# FPGAPower_Misc.net
KiCad netlist of a schematic drawn in Altium Designer
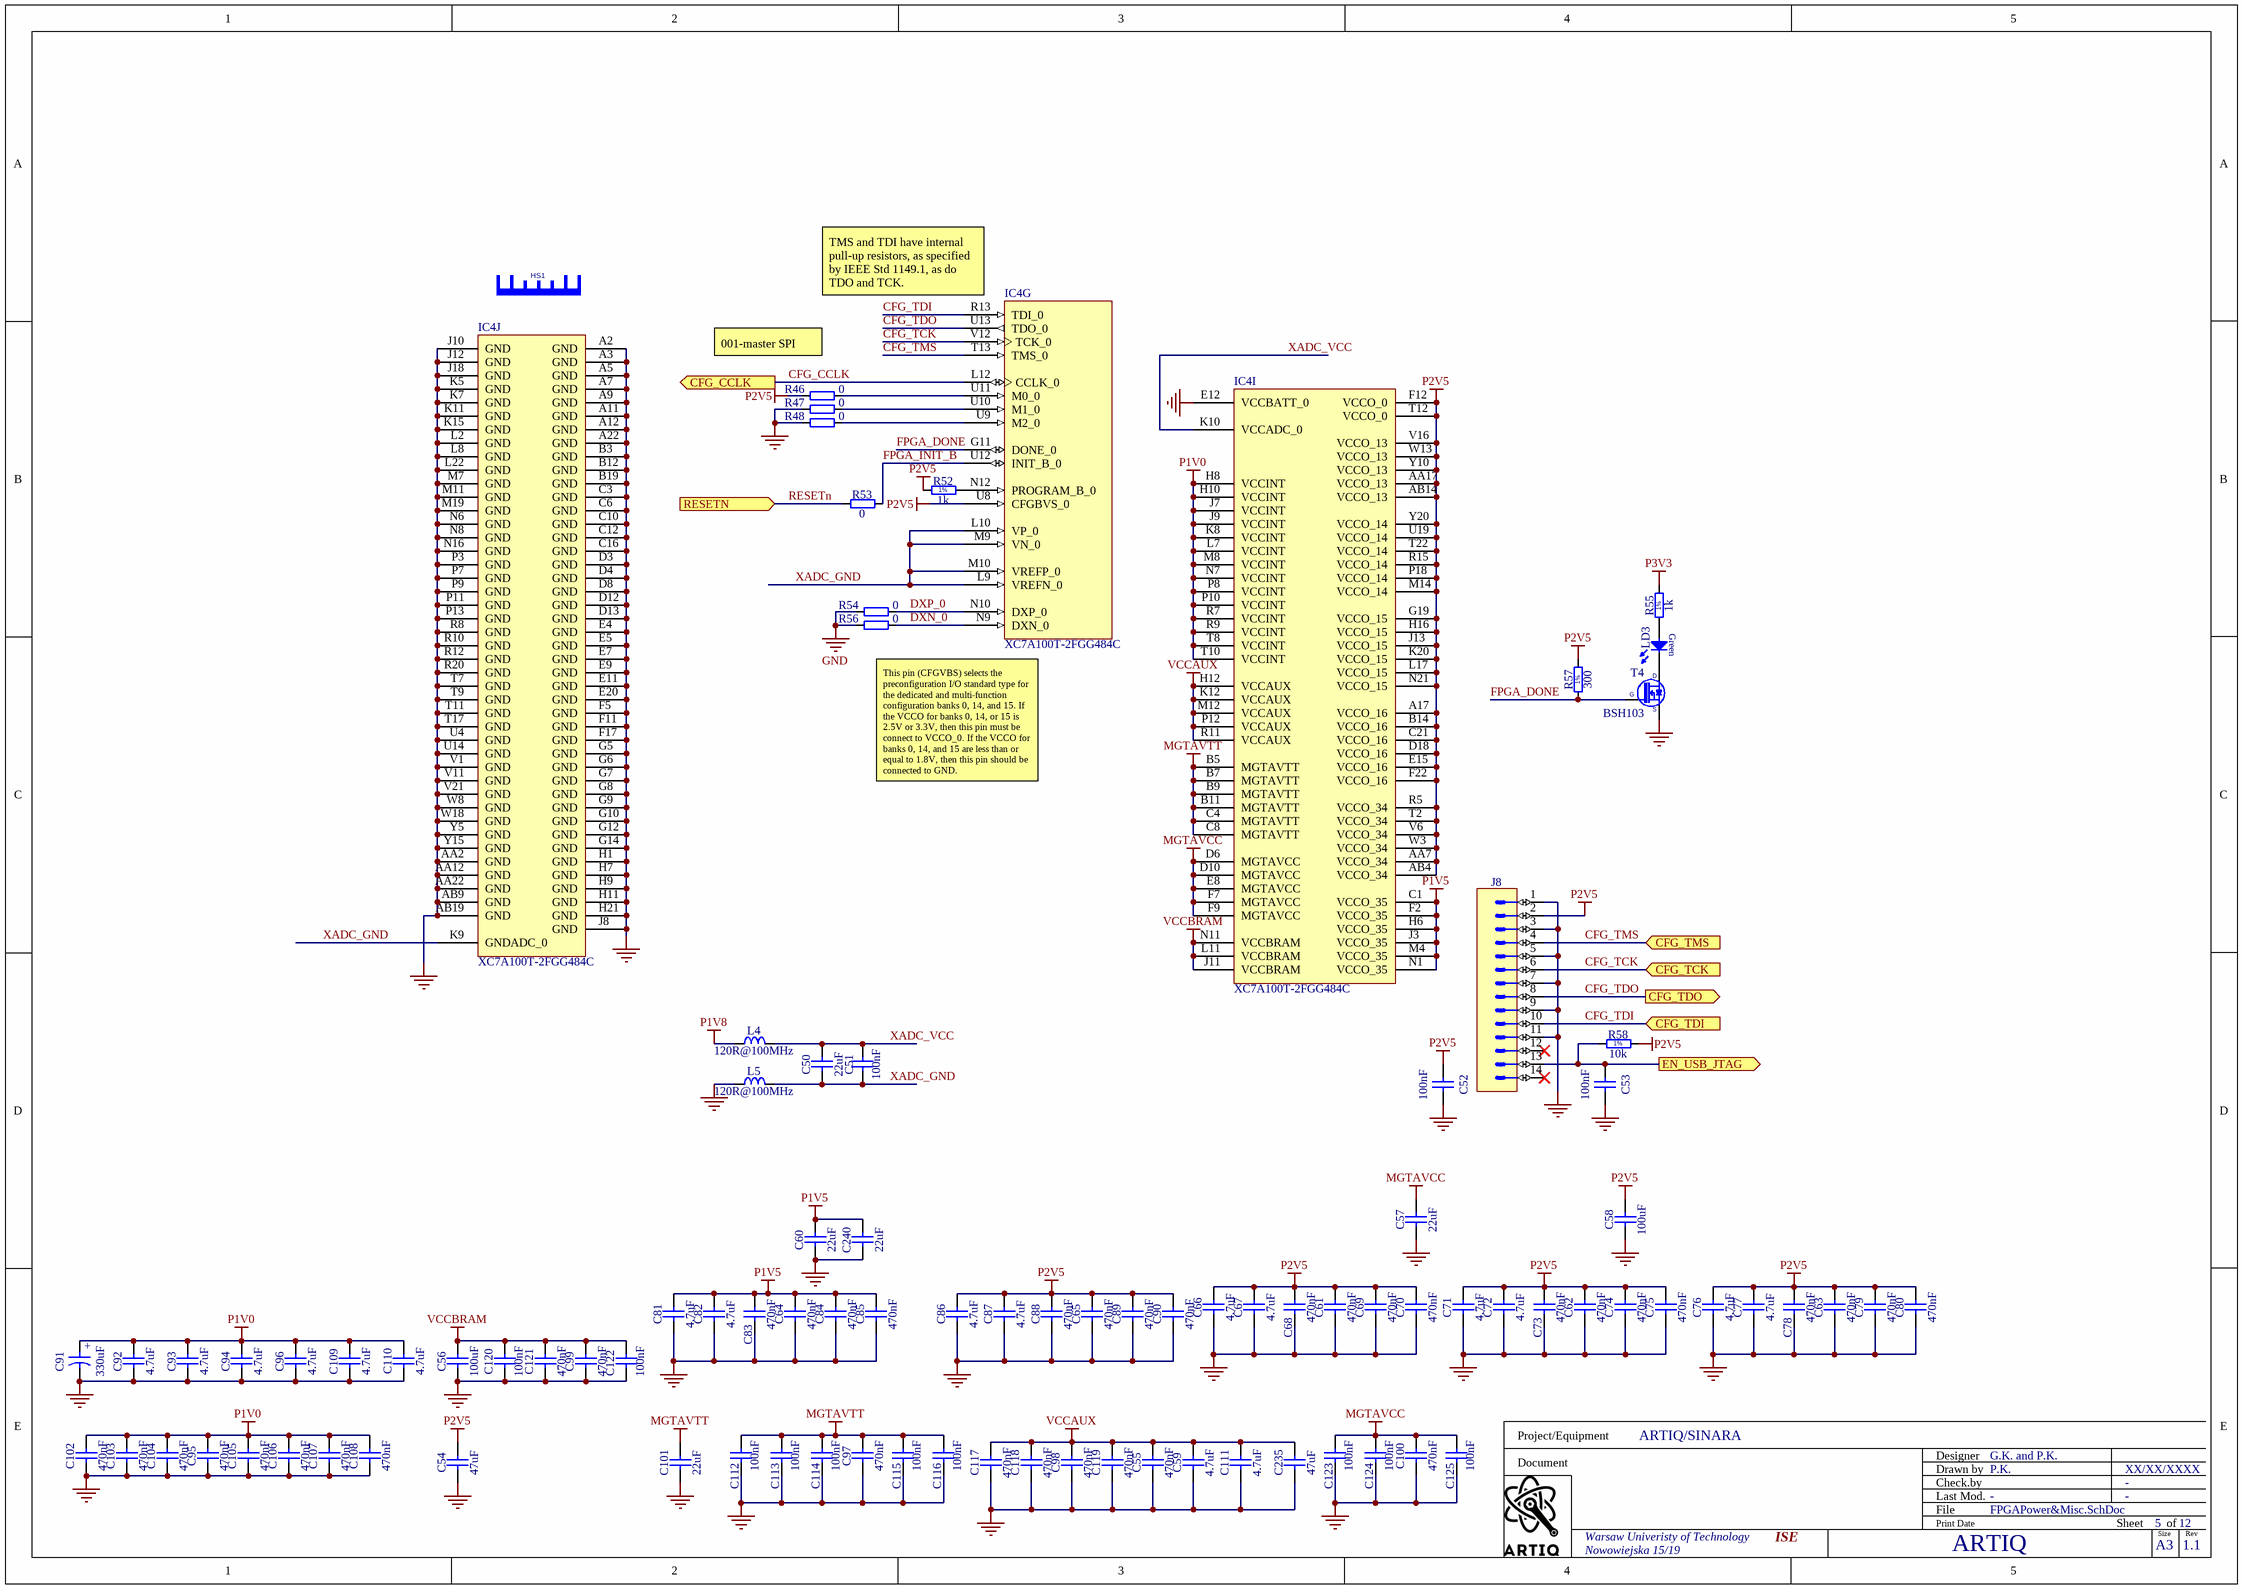
[diagram p0: FPGAPower&Misc.SchDoc]

(export (version "E")
  (design (tool "Eeschema 10.0.6"))
  (components
    (comp (ref "C50")
      (value "22uF")
      (footprint "CAPC1709X100N")
      (description "Non-polarised capacitor")
      (fields
        (field (name "PART NUMBER") "CC0603_22UF_6.3V_20%_X5R")
        (field (name "VOLTAGE") "6.3V")
        (field (name "AUTHOR") "CERN DEM JLC")
      )
      (libsource (lib "Capacitors") (part "Capacitor - non polarized"))
    )
    (comp (ref "C51")
      (value "100nF")
      (footprint "CAPC0603X33N")
      (description "Non-polarised capacitor")
      (fields
        (field (name "PART NUMBER") "CC0201_100NF_6.3V_10%_X5R")
        (field (name "VOLTAGE") "6.3V")
        (field (name "AUTHOR") "CERN DEM JLC")
      )
      (libsource (lib "Capacitors") (part "Capacitor - non polarized"))
    )
    (comp (ref "C52")
      (value "100nF")
      (footprint "CAPC0603X33N")
      (description "Non-polarised capacitor")
      (fields
        (field (name "PART NUMBER") "CC0201_100NF_6.3V_10%_X5R")
        (field (name "VOLTAGE") "6.3V")
        (field (name "AUTHOR") "CERN DEM JLC")
      )
      (libsource (lib "Capacitors") (part "Capacitor - non polarized"))
    )
    (comp (ref "C53")
      (value "100nF")
      (footprint "CAPC0603X33N")
      (description "Non-polarised capacitor")
      (fields
        (field (name "PART NUMBER") "CC0201_100NF_6.3V_10%_X5R")
        (field (name "VOLTAGE") "6.3V")
        (field (name "AUTHOR") "CERN DEM JLC")
      )
      (libsource (lib "Capacitors") (part "Capacitor - non polarized"))
    )
    (comp (ref "C54")
      (value "47uF")
      (footprint "CAPC3225X270N")
      (description "Non-polarised capacitor")
      (fields
        (field (name "PART NUMBER") "CC1210_47UF_10V_10%_X7R")
        (field (name "VOLTAGE") "10V")
        (field (name "AUTHOR") "CERN DEM BC")
      )
      (libsource (lib "Capacitors") (part "Capacitor - non polarized"))
    )
    (comp (ref "C55")
      (value "470nF")
      (footprint "CAPC0603X33N")
      (description "Non-polarised capacitor")
      (fields
        (field (name "PART NUMBER") "CC0201_470NF_4V_20%_X5R")
        (field (name "VOLTAGE") "4V")
        (field (name "AUTHOR") "CERN DEM JLC")
      )
      (libsource (lib "Capacitors") (part "Capacitor - non polarized"))
    )
    (comp (ref "C56")
      (value "100uF")
      (footprint "CAPC3225X270N")
      (description "Non-polarised capacitor")
      (fields
        (field (name "PART NUMBER") "CC1210_100UF_6.3V_20%_X5R")
        (field (name "VOLTAGE") "6.3V")
        (field (name "AUTHOR") "CERN DEM JLC")
      )
      (libsource (lib "Capacitors") (part "Capacitor - non polarized"))
    )
    (comp (ref "C57")
      (value "22uF")
      (footprint "CAPC1709X100N")
      (description "Non-polarised capacitor")
      (fields
        (field (name "PART NUMBER") "CC0603_22UF_6.3V_20%_X5R")
        (field (name "VOLTAGE") "6.3V")
        (field (name "AUTHOR") "CERN DEM JLC")
      )
      (libsource (lib "Capacitors") (part "Capacitor - non polarized"))
    )
    (comp (ref "C58")
      (value "100uF")
      (footprint "CAPC3225X270N")
      (description "Non-polarised capacitor")
      (fields
        (field (name "PART NUMBER") "CC1210_100UF_6.3V_20%_X5R")
        (field (name "VOLTAGE") "6.3V")
        (field (name "AUTHOR") "CERN DEM JLC")
      )
      (libsource (lib "Capacitors") (part "Capacitor - non polarized"))
    )
    (comp (ref "C59")
      (value "4.7uF")
      (footprint "CAPC2012X135N")
      (description "Non-polarised capacitor")
      (fields
        (field (name "MANUFACTURER") "GENERIC")
        (field (name "PART NUMBER") "CC0805_4.7UF_10V_10%_X5R")
        (field (name "AUTHOR") "CERN DEM JLC")
      )
      (libsource (lib "Capacitors") (part "Capacitor - non polarized"))
    )
    (comp (ref "C60")
      (value "22uF")
      (footprint "CAPC1709X100N")
      (description "Non-polarised capacitor")
      (fields
        (field (name "PART NUMBER") "CC0603_22UF_6.3V_20%_X5R")
        (field (name "VOLTAGE") "6.3V")
        (field (name "AUTHOR") "CERN DEM JLC")
      )
      (libsource (lib "Capacitors") (part "Capacitor - non polarized"))
    )
    (comp (ref "C61")
      (value "470nF")
      (footprint "CAPC0603X33N")
      (description "Non-polarised capacitor")
      (fields
        (field (name "PART NUMBER") "CC0201_470NF_4V_20%_X5R")
        (field (name "VOLTAGE") "4V")
        (field (name "AUTHOR") "CERN DEM JLC")
      )
      (libsource (lib "Capacitors") (part "Capacitor - non polarized"))
    )
    (comp (ref "C62")
      (value "470nF")
      (footprint "CAPC0603X33N")
      (description "Non-polarised capacitor")
      (fields
        (field (name "PART NUMBER") "CC0201_470NF_4V_20%_X5R")
        (field (name "VOLTAGE") "4V")
        (field (name "AUTHOR") "CERN DEM JLC")
      )
      (libsource (lib "Capacitors") (part "Capacitor - non polarized"))
    )
    (comp (ref "C63")
      (value "470nF")
      (footprint "CAPC0603X33N")
      (description "Non-polarised capacitor")
      (fields
        (field (name "PART NUMBER") "CC0201_470NF_4V_20%_X5R")
        (field (name "VOLTAGE") "4V")
        (field (name "AUTHOR") "CERN DEM JLC")
      )
      (libsource (lib "Capacitors") (part "Capacitor - non polarized"))
    )
    (comp (ref "C64")
      (value "470nF")
      (footprint "CAPC0603X33N")
      (description "Non-polarised capacitor")
      (fields
        (field (name "PART NUMBER") "CC0201_470NF_4V_20%_X5R")
        (field (name "VOLTAGE") "4V")
        (field (name "AUTHOR") "CERN DEM JLC")
      )
      (libsource (lib "Capacitors") (part "Capacitor - non polarized"))
    )
    (comp (ref "C65")
      (value "470nF")
      (footprint "CAPC0603X33N")
      (description "Non-polarised capacitor")
      (fields
        (field (name "PART NUMBER") "CC0201_470NF_4V_20%_X5R")
        (field (name "VOLTAGE") "4V")
        (field (name "AUTHOR") "CERN DEM JLC")
      )
      (libsource (lib "Capacitors") (part "Capacitor - non polarized"))
    )
    (comp (ref "C66")
      (value "4.7uF")
      (footprint "CAPC2012X135N")
      (description "Non-polarised capacitor")
      (fields
        (field (name "MANUFACTURER") "GENERIC")
        (field (name "PART NUMBER") "CC0805_4.7UF_10V_10%_X5R")
        (field (name "AUTHOR") "CERN DEM JLC")
      )
      (libsource (lib "Capacitors") (part "Capacitor - non polarized"))
    )
    (comp (ref "C67")
      (value "4.7uF")
      (footprint "CAPC2012X135N")
      (description "Non-polarised capacitor")
      (fields
        (field (name "MANUFACTURER") "GENERIC")
        (field (name "PART NUMBER") "CC0805_4.7UF_10V_10%_X5R")
        (field (name "AUTHOR") "CERN DEM JLC")
      )
      (libsource (lib "Capacitors") (part "Capacitor - non polarized"))
    )
    (comp (ref "C68")
      (value "470nF")
      (footprint "CAPC0603X33N")
      (description "Non-polarised capacitor")
      (fields
        (field (name "PART NUMBER") "CC0201_470NF_4V_20%_X5R")
        (field (name "VOLTAGE") "4V")
        (field (name "AUTHOR") "CERN DEM JLC")
      )
      (libsource (lib "Capacitors") (part "Capacitor - non polarized"))
    )
    (comp (ref "C69")
      (value "470nF")
      (footprint "CAPC0603X33N")
      (description "Non-polarised capacitor")
      (fields
        (field (name "PART NUMBER") "CC0201_470NF_4V_20%_X5R")
        (field (name "VOLTAGE") "4V")
        (field (name "AUTHOR") "CERN DEM JLC")
      )
      (libsource (lib "Capacitors") (part "Capacitor - non polarized"))
    )
    (comp (ref "C70")
      (value "470nF")
      (footprint "CAPC0603X33N")
      (description "Non-polarised capacitor")
      (fields
        (field (name "PART NUMBER") "CC0201_470NF_4V_20%_X5R")
        (field (name "VOLTAGE") "4V")
        (field (name "AUTHOR") "CERN DEM JLC")
      )
      (libsource (lib "Capacitors") (part "Capacitor - non polarized"))
    )
    (comp (ref "C71")
      (value "4.7uF")
      (footprint "CAPC2012X135N")
      (description "Non-polarised capacitor")
      (fields
        (field (name "MANUFACTURER") "GENERIC")
        (field (name "PART NUMBER") "CC0805_4.7UF_10V_10%_X5R")
        (field (name "AUTHOR") "CERN DEM JLC")
      )
      (libsource (lib "Capacitors") (part "Capacitor - non polarized"))
    )
    (comp (ref "C72")
      (value "4.7uF")
      (footprint "CAPC2012X135N")
      (description "Non-polarised capacitor")
      (fields
        (field (name "MANUFACTURER") "GENERIC")
        (field (name "PART NUMBER") "CC0805_4.7UF_10V_10%_X5R")
        (field (name "AUTHOR") "CERN DEM JLC")
      )
      (libsource (lib "Capacitors") (part "Capacitor - non polarized"))
    )
    (comp (ref "C73")
      (value "470nF")
      (footprint "CAPC0603X33N")
      (description "Non-polarised capacitor")
      (fields
        (field (name "PART NUMBER") "CC0201_470NF_4V_20%_X5R")
        (field (name "VOLTAGE") "4V")
        (field (name "AUTHOR") "CERN DEM JLC")
      )
      (libsource (lib "Capacitors") (part "Capacitor - non polarized"))
    )
    (comp (ref "C74")
      (value "470nF")
      (footprint "CAPC0603X33N")
      (description "Non-polarised capacitor")
      (fields
        (field (name "PART NUMBER") "CC0201_470NF_4V_20%_X5R")
        (field (name "VOLTAGE") "4V")
        (field (name "AUTHOR") "CERN DEM JLC")
      )
      (libsource (lib "Capacitors") (part "Capacitor - non polarized"))
    )
    (comp (ref "C75")
      (value "470nF")
      (footprint "CAPC0603X33N")
      (description "Non-polarised capacitor")
      (fields
        (field (name "PART NUMBER") "CC0201_470NF_4V_20%_X5R")
        (field (name "VOLTAGE") "4V")
        (field (name "AUTHOR") "CERN DEM JLC")
      )
      (libsource (lib "Capacitors") (part "Capacitor - non polarized"))
    )
    (comp (ref "C76")
      (value "4.7uF")
      (footprint "CAPC2012X135N")
      (description "Non-polarised capacitor")
      (fields
        (field (name "MANUFACTURER") "GENERIC")
        (field (name "PART NUMBER") "CC0805_4.7UF_10V_10%_X5R")
        (field (name "AUTHOR") "CERN DEM JLC")
      )
      (libsource (lib "Capacitors") (part "Capacitor - non polarized"))
    )
    (comp (ref "C77")
      (value "4.7uF")
      (footprint "CAPC2012X135N")
      (description "Non-polarised capacitor")
      (fields
        (field (name "MANUFACTURER") "GENERIC")
        (field (name "PART NUMBER") "CC0805_4.7UF_10V_10%_X5R")
        (field (name "AUTHOR") "CERN DEM JLC")
      )
      (libsource (lib "Capacitors") (part "Capacitor - non polarized"))
    )
    (comp (ref "C78")
      (value "470nF")
      (footprint "CAPC0603X33N")
      (description "Non-polarised capacitor")
      (fields
        (field (name "PART NUMBER") "CC0201_470NF_4V_20%_X5R")
        (field (name "VOLTAGE") "4V")
        (field (name "AUTHOR") "CERN DEM JLC")
      )
      (libsource (lib "Capacitors") (part "Capacitor - non polarized"))
    )
    (comp (ref "C79")
      (value "470nF")
      (footprint "CAPC0603X33N")
      (description "Non-polarised capacitor")
      (fields
        (field (name "PART NUMBER") "CC0201_470NF_4V_20%_X5R")
        (field (name "VOLTAGE") "4V")
        (field (name "AUTHOR") "CERN DEM JLC")
      )
      (libsource (lib "Capacitors") (part "Capacitor - non polarized"))
    )
    (comp (ref "C80")
      (value "470nF")
      (footprint "CAPC0603X33N")
      (description "Non-polarised capacitor")
      (fields
        (field (name "PART NUMBER") "CC0201_470NF_4V_20%_X5R")
        (field (name "VOLTAGE") "4V")
        (field (name "AUTHOR") "CERN DEM JLC")
      )
      (libsource (lib "Capacitors") (part "Capacitor - non polarized"))
    )
    (comp (ref "C81")
      (value "4.7uF")
      (footprint "CAPC2012X135N")
      (description "Non-polarised capacitor")
      (fields
        (field (name "MANUFACTURER") "GENERIC")
        (field (name "PART NUMBER") "CC0805_4.7UF_10V_10%_X5R")
        (field (name "AUTHOR") "CERN DEM JLC")
      )
      (libsource (lib "Capacitors") (part "Capacitor - non polarized"))
    )
    (comp (ref "C82")
      (value "4.7uF")
      (footprint "CAPC2012X135N")
      (description "Non-polarised capacitor")
      (fields
        (field (name "MANUFACTURER") "GENERIC")
        (field (name "PART NUMBER") "CC0805_4.7UF_10V_10%_X5R")
        (field (name "AUTHOR") "CERN DEM JLC")
      )
      (libsource (lib "Capacitors") (part "Capacitor - non polarized"))
    )
    (comp (ref "C83")
      (value "470nF")
      (footprint "CAPC0603X33N")
      (description "Non-polarised capacitor")
      (fields
        (field (name "PART NUMBER") "CC0201_470NF_4V_20%_X5R")
        (field (name "VOLTAGE") "4V")
        (field (name "AUTHOR") "CERN DEM JLC")
      )
      (libsource (lib "Capacitors") (part "Capacitor - non polarized"))
    )
    (comp (ref "C84")
      (value "470nF")
      (footprint "CAPC0603X33N")
      (description "Non-polarised capacitor")
      (fields
        (field (name "PART NUMBER") "CC0201_470NF_4V_20%_X5R")
        (field (name "VOLTAGE") "4V")
        (field (name "AUTHOR") "CERN DEM JLC")
      )
      (libsource (lib "Capacitors") (part "Capacitor - non polarized"))
    )
    (comp (ref "C85")
      (value "470nF")
      (footprint "CAPC0603X33N")
      (description "Non-polarised capacitor")
      (fields
        (field (name "PART NUMBER") "CC0201_470NF_4V_20%_X5R")
        (field (name "VOLTAGE") "4V")
        (field (name "AUTHOR") "CERN DEM JLC")
      )
      (libsource (lib "Capacitors") (part "Capacitor - non polarized"))
    )
    (comp (ref "C86")
      (value "4.7uF")
      (footprint "CAPC2012X135N")
      (description "Non-polarised capacitor")
      (fields
        (field (name "MANUFACTURER") "GENERIC")
        (field (name "PART NUMBER") "CC0805_4.7UF_10V_10%_X5R")
        (field (name "AUTHOR") "CERN DEM JLC")
      )
      (libsource (lib "Capacitors") (part "Capacitor - non polarized"))
    )
    (comp (ref "C87")
      (value "4.7uF")
      (footprint "CAPC2012X135N")
      (description "Non-polarised capacitor")
      (fields
        (field (name "MANUFACTURER") "GENERIC")
        (field (name "PART NUMBER") "CC0805_4.7UF_10V_10%_X5R")
        (field (name "AUTHOR") "CERN DEM JLC")
      )
      (libsource (lib "Capacitors") (part "Capacitor - non polarized"))
    )
    (comp (ref "C88")
      (value "470nF")
      (footprint "CAPC0603X33N")
      (description "Non-polarised capacitor")
      (fields
        (field (name "PART NUMBER") "CC0201_470NF_4V_20%_X5R")
        (field (name "VOLTAGE") "4V")
        (field (name "AUTHOR") "CERN DEM JLC")
      )
      (libsource (lib "Capacitors") (part "Capacitor - non polarized"))
    )
    (comp (ref "C89")
      (value "470nF")
      (footprint "CAPC0603X33N")
      (description "Non-polarised capacitor")
      (fields
        (field (name "PART NUMBER") "CC0201_470NF_4V_20%_X5R")
        (field (name "VOLTAGE") "4V")
        (field (name "AUTHOR") "CERN DEM JLC")
      )
      (libsource (lib "Capacitors") (part "Capacitor - non polarized"))
    )
    (comp (ref "C90")
      (value "470nF")
      (footprint "CAPC0603X33N")
      (description "Non-polarised capacitor")
      (fields
        (field (name "PART NUMBER") "CC0201_470NF_4V_20%_X5R")
        (field (name "VOLTAGE") "4V")
        (field (name "AUTHOR") "CERN DEM JLC")
      )
      (libsource (lib "Capacitors") (part "Capacitor - non polarized"))
    )
    (comp (ref "C91")
      (value "330uF")
      (footprint "CAPMP7343X190N")
      (description "Polarised capacitor")
      (fields
        (field (name "PART NUMBER") "CTE7343-19_330UF_2.5V_20%_LESR0025_KEMET_T520")
        (field (name "VOLTAGE") "2.5V")
        (field (name "AUTHOR") "CERN DEM MR")
      )
      (libsource (lib "Capacitors") (part "Capacitor - polarized"))
    )
    (comp (ref "C92")
      (value "4.7uF")
      (footprint "CAPC2012X135N")
      (description "Non-polarised capacitor")
      (fields
        (field (name "MANUFACTURER") "GENERIC")
        (field (name "PART NUMBER") "CC0805_4.7UF_10V_10%_X5R")
        (field (name "AUTHOR") "CERN DEM JLC")
      )
      (libsource (lib "Capacitors") (part "Capacitor - non polarized"))
    )
    (comp (ref "C93")
      (value "4.7uF")
      (footprint "CAPC2012X135N")
      (description "Non-polarised capacitor")
      (fields
        (field (name "MANUFACTURER") "GENERIC")
        (field (name "PART NUMBER") "CC0805_4.7UF_10V_10%_X5R")
        (field (name "AUTHOR") "CERN DEM JLC")
      )
      (libsource (lib "Capacitors") (part "Capacitor - non polarized"))
    )
    (comp (ref "C94")
      (value "4.7uF")
      (footprint "CAPC2012X135N")
      (description "Non-polarised capacitor")
      (fields
        (field (name "MANUFACTURER") "GENERIC")
        (field (name "PART NUMBER") "CC0805_4.7UF_10V_10%_X5R")
        (field (name "AUTHOR") "CERN DEM JLC")
      )
      (libsource (lib "Capacitors") (part "Capacitor - non polarized"))
    )
    (comp (ref "C95")
      (value "470nF")
      (footprint "CAPC0603X33N")
      (description "Non-polarised capacitor")
      (fields
        (field (name "PART NUMBER") "CC0201_470NF_4V_20%_X5R")
        (field (name "VOLTAGE") "4V")
        (field (name "AUTHOR") "CERN DEM JLC")
      )
      (libsource (lib "Capacitors") (part "Capacitor - non polarized"))
    )
    (comp (ref "C96")
      (value "4.7uF")
      (footprint "CAPC2012X135N")
      (description "Non-polarised capacitor")
      (fields
        (field (name "MANUFACTURER") "GENERIC")
        (field (name "PART NUMBER") "CC0805_4.7UF_10V_10%_X5R")
        (field (name "AUTHOR") "CERN DEM JLC")
      )
      (libsource (lib "Capacitors") (part "Capacitor - non polarized"))
    )
    (comp (ref "C97")
      (value "470nF")
      (footprint "CAPC0603X33N")
      (description "Non-polarised capacitor")
      (fields
        (field (name "PART NUMBER") "CC0201_470NF_4V_20%_X5R")
        (field (name "VOLTAGE") "4V")
        (field (name "AUTHOR") "CERN DEM JLC")
      )
      (libsource (lib "Capacitors") (part "Capacitor - non polarized"))
    )
    (comp (ref "C98")
      (value "470nF")
      (footprint "CAPC0603X33N")
      (description "Non-polarised capacitor")
      (fields
        (field (name "PART NUMBER") "CC0201_470NF_4V_20%_X5R")
        (field (name "VOLTAGE") "4V")
        (field (name "AUTHOR") "CERN DEM JLC")
      )
      (libsource (lib "Capacitors") (part "Capacitor - non polarized"))
    )
    (comp (ref "C99")
      (value "470nF")
      (footprint "CAPC0603X33N")
      (description "Non-polarised capacitor")
      (fields
        (field (name "PART NUMBER") "CC0201_470NF_4V_20%_X5R")
        (field (name "VOLTAGE") "4V")
        (field (name "AUTHOR") "CERN DEM JLC")
      )
      (libsource (lib "Capacitors") (part "Capacitor - non polarized"))
    )
    (comp (ref "C100")
      (value "470nF")
      (footprint "CAPC0603X33N")
      (description "Non-polarised capacitor")
      (fields
        (field (name "PART NUMBER") "CC0201_470NF_4V_20%_X5R")
        (field (name "VOLTAGE") "4V")
        (field (name "AUTHOR") "CERN DEM JLC")
      )
      (libsource (lib "Capacitors") (part "Capacitor - non polarized"))
    )
    (comp (ref "C101")
      (value "22uF")
      (footprint "CAPC1709X100N")
      (description "Non-polarised capacitor")
      (fields
        (field (name "PART NUMBER") "CC0603_22UF_6.3V_20%_X5R")
        (field (name "VOLTAGE") "6.3V")
        (field (name "AUTHOR") "CERN DEM JLC")
      )
      (libsource (lib "Capacitors") (part "Capacitor - non polarized"))
    )
    (comp (ref "C102")
      (value "470nF")
      (footprint "CAPC0603X33N")
      (description "Non-polarised capacitor")
      (fields
        (field (name "PART NUMBER") "CC0201_470NF_4V_20%_X5R")
        (field (name "VOLTAGE") "4V")
        (field (name "AUTHOR") "CERN DEM JLC")
      )
      (libsource (lib "Capacitors") (part "Capacitor - non polarized"))
    )
    (comp (ref "C103")
      (value "470nF")
      (footprint "CAPC0603X33N")
      (description "Non-polarised capacitor")
      (fields
        (field (name "PART NUMBER") "CC0201_470NF_4V_20%_X5R")
        (field (name "VOLTAGE") "4V")
        (field (name "AUTHOR") "CERN DEM JLC")
      )
      (libsource (lib "Capacitors") (part "Capacitor - non polarized"))
    )
    (comp (ref "C104")
      (value "470nF")
      (footprint "CAPC0603X33N")
      (description "Non-polarised capacitor")
      (fields
        (field (name "PART NUMBER") "CC0201_470NF_4V_20%_X5R")
        (field (name "VOLTAGE") "4V")
        (field (name "AUTHOR") "CERN DEM JLC")
      )
      (libsource (lib "Capacitors") (part "Capacitor - non polarized"))
    )
    (comp (ref "C105")
      (value "470nF")
      (footprint "CAPC0603X33N")
      (description "Non-polarised capacitor")
      (fields
        (field (name "PART NUMBER") "CC0201_470NF_4V_20%_X5R")
        (field (name "VOLTAGE") "4V")
        (field (name "AUTHOR") "CERN DEM JLC")
      )
      (libsource (lib "Capacitors") (part "Capacitor - non polarized"))
    )
    (comp (ref "C106")
      (value "470nF")
      (footprint "CAPC0603X33N")
      (description "Non-polarised capacitor")
      (fields
        (field (name "PART NUMBER") "CC0201_470NF_4V_20%_X5R")
        (field (name "VOLTAGE") "4V")
        (field (name "AUTHOR") "CERN DEM JLC")
      )
      (libsource (lib "Capacitors") (part "Capacitor - non polarized"))
    )
    (comp (ref "C107")
      (value "470nF")
      (footprint "CAPC0603X33N")
      (description "Non-polarised capacitor")
      (fields
        (field (name "PART NUMBER") "CC0201_470NF_4V_20%_X5R")
        (field (name "VOLTAGE") "4V")
        (field (name "AUTHOR") "CERN DEM JLC")
      )
      (libsource (lib "Capacitors") (part "Capacitor - non polarized"))
    )
    (comp (ref "C108")
      (value "470nF")
      (footprint "CAPC0603X33N")
      (description "Non-polarised capacitor")
      (fields
        (field (name "PART NUMBER") "CC0201_470NF_4V_20%_X5R")
        (field (name "VOLTAGE") "4V")
        (field (name "AUTHOR") "CERN DEM JLC")
      )
      (libsource (lib "Capacitors") (part "Capacitor - non polarized"))
    )
    (comp (ref "C109")
      (value "4.7uF")
      (footprint "CAPC2012X135N")
      (description "Non-polarised capacitor")
      (fields
        (field (name "MANUFACTURER") "GENERIC")
        (field (name "PART NUMBER") "CC0805_4.7UF_10V_10%_X5R")
        (field (name "AUTHOR") "CERN DEM JLC")
      )
      (libsource (lib "Capacitors") (part "Capacitor - non polarized"))
    )
    (comp (ref "C110")
      (value "4.7uF")
      (footprint "CAPC2012X135N")
      (description "Non-polarised capacitor")
      (fields
        (field (name "MANUFACTURER") "GENERIC")
        (field (name "PART NUMBER") "CC0805_4.7UF_10V_10%_X5R")
        (field (name "AUTHOR") "CERN DEM JLC")
      )
      (libsource (lib "Capacitors") (part "Capacitor - non polarized"))
    )
    (comp (ref "C111")
      (value "4.7uF")
      (footprint "CAPC2012X135N")
      (description "Non-polarised capacitor")
      (fields
        (field (name "MANUFACTURER") "GENERIC")
        (field (name "PART NUMBER") "CC0805_4.7UF_10V_10%_X5R")
        (field (name "AUTHOR") "CERN DEM JLC")
      )
      (libsource (lib "Capacitors") (part "Capacitor - non polarized"))
    )
    (comp (ref "C112")
      (value "100nF")
      (footprint "CAPC0603X33N")
      (description "Non-polarised capacitor")
      (fields
        (field (name "PART NUMBER") "CC0201_100NF_6.3V_10%_X5R")
        (field (name "VOLTAGE") "6.3V")
        (field (name "AUTHOR") "CERN DEM JLC")
      )
      (libsource (lib "Capacitors") (part "Capacitor - non polarized"))
    )
    (comp (ref "C113")
      (value "100nF")
      (footprint "CAPC0603X33N")
      (description "Non-polarised capacitor")
      (fields
        (field (name "PART NUMBER") "CC0201_100NF_6.3V_10%_X5R")
        (field (name "VOLTAGE") "6.3V")
        (field (name "AUTHOR") "CERN DEM JLC")
      )
      (libsource (lib "Capacitors") (part "Capacitor - non polarized"))
    )
    (comp (ref "C114")
      (value "100nF")
      (footprint "CAPC0603X33N")
      (description "Non-polarised capacitor")
      (fields
        (field (name "PART NUMBER") "CC0201_100NF_6.3V_10%_X5R")
        (field (name "VOLTAGE") "6.3V")
        (field (name "AUTHOR") "CERN DEM JLC")
      )
      (libsource (lib "Capacitors") (part "Capacitor - non polarized"))
    )
    (comp (ref "C115")
      (value "100nF")
      (footprint "CAPC0603X33N")
      (description "Non-polarised capacitor")
      (fields
        (field (name "PART NUMBER") "CC0201_100NF_6.3V_10%_X5R")
        (field (name "VOLTAGE") "6.3V")
        (field (name "AUTHOR") "CERN DEM JLC")
      )
      (libsource (lib "Capacitors") (part "Capacitor - non polarized"))
    )
    (comp (ref "C116")
      (value "100nF")
      (footprint "CAPC0603X33N")
      (description "Non-polarised capacitor")
      (fields
        (field (name "PART NUMBER") "CC0201_100NF_6.3V_10%_X5R")
        (field (name "VOLTAGE") "6.3V")
        (field (name "AUTHOR") "CERN DEM JLC")
      )
      (libsource (lib "Capacitors") (part "Capacitor - non polarized"))
    )
    (comp (ref "C117")
      (value "470nF")
      (footprint "CAPC0603X33N")
      (description "Non-polarised capacitor")
      (fields
        (field (name "PART NUMBER") "CC0201_470NF_4V_20%_X5R")
        (field (name "VOLTAGE") "4V")
        (field (name "AUTHOR") "CERN DEM JLC")
      )
      (libsource (lib "Capacitors") (part "Capacitor - non polarized"))
    )
    (comp (ref "C118")
      (value "470nF")
      (footprint "CAPC0603X33N")
      (description "Non-polarised capacitor")
      (fields
        (field (name "PART NUMBER") "CC0201_470NF_4V_20%_X5R")
        (field (name "VOLTAGE") "4V")
        (field (name "AUTHOR") "CERN DEM JLC")
      )
      (libsource (lib "Capacitors") (part "Capacitor - non polarized"))
    )
    (comp (ref "C119")
      (value "470nF")
      (footprint "CAPC0603X33N")
      (description "Non-polarised capacitor")
      (fields
        (field (name "PART NUMBER") "CC0201_470NF_4V_20%_X5R")
        (field (name "VOLTAGE") "4V")
        (field (name "AUTHOR") "CERN DEM JLC")
      )
      (libsource (lib "Capacitors") (part "Capacitor - non polarized"))
    )
    (comp (ref "C120")
      (value "100nF")
      (footprint "CAPC0603X33N")
      (description "Non-polarised capacitor")
      (fields
        (field (name "PART NUMBER") "CC0201_100NF_6.3V_10%_X5R")
        (field (name "VOLTAGE") "6.3V")
        (field (name "AUTHOR") "CERN DEM JLC")
      )
      (libsource (lib "Capacitors") (part "Capacitor - non polarized"))
    )
    (comp (ref "C121")
      (value "470nF")
      (footprint "CAPC0603X33N")
      (description "Non-polarised capacitor")
      (fields
        (field (name "PART NUMBER") "CC0201_470NF_4V_20%_X5R")
        (field (name "VOLTAGE") "4V")
        (field (name "AUTHOR") "CERN DEM JLC")
      )
      (libsource (lib "Capacitors") (part "Capacitor - non polarized"))
    )
    (comp (ref "C122")
      (value "100nF")
      (footprint "CAPC0603X33N")
      (description "Non-polarised capacitor")
      (fields
        (field (name "PART NUMBER") "CC0201_100NF_6.3V_10%_X5R")
        (field (name "VOLTAGE") "6.3V")
        (field (name "AUTHOR") "CERN DEM JLC")
      )
      (libsource (lib "Capacitors") (part "Capacitor - non polarized"))
    )
    (comp (ref "C123")
      (value "100nF")
      (footprint "CAPC0603X33N")
      (description "Non-polarised capacitor")
      (fields
        (field (name "PART NUMBER") "CC0201_100NF_6.3V_10%_X5R")
        (field (name "VOLTAGE") "6.3V")
        (field (name "AUTHOR") "CERN DEM JLC")
      )
      (libsource (lib "Capacitors") (part "Capacitor - non polarized"))
    )
    (comp (ref "C124")
      (value "100nF")
      (footprint "CAPC0603X33N")
      (description "Non-polarised capacitor")
      (fields
        (field (name "PART NUMBER") "CC0201_100NF_6.3V_10%_X5R")
        (field (name "VOLTAGE") "6.3V")
        (field (name "AUTHOR") "CERN DEM JLC")
      )
      (libsource (lib "Capacitors") (part "Capacitor - non polarized"))
    )
    (comp (ref "C125")
      (value "100nF")
      (footprint "CAPC0603X33N")
      (description "Non-polarised capacitor")
      (fields
        (field (name "PART NUMBER") "CC0201_100NF_6.3V_10%_X5R")
        (field (name "VOLTAGE") "6.3V")
        (field (name "AUTHOR") "CERN DEM JLC")
      )
      (libsource (lib "Capacitors") (part "Capacitor - non polarized"))
    )
    (comp (ref "C235")
      (value "47uF")
      (footprint "CAPC3225X270N")
      (description "Non-polarised capacitor")
      (fields
        (field (name "PART NUMBER") "CC1210_47UF_10V_10%_X7R")
        (field (name "VOLTAGE") "10V")
        (field (name "AUTHOR") "CERN DEM BC")
      )
      (libsource (lib "Capacitors") (part "Capacitor - non polarized"))
    )
    (comp (ref "C240")
      (value "22uF")
      (footprint "CAPC1709X100N")
      (description "Non-polarised capacitor")
      (fields
        (field (name "PART NUMBER") "CC0603_22UF_6.3V_20%_X5R")
        (field (name "VOLTAGE") "6.3V")
        (field (name "AUTHOR") "CERN DEM JLC")
      )
      (libsource (lib "Capacitors") (part "Capacitor - non polarized"))
    )
    (comp (ref "HS1")
      (value "Heat Sink No Pad")
      (footprint "ICK BGA 23 x 23 x 10")
      (description "Heat Sink Without Pad")
      (fields
        (field (name "MANUFACTURER") "Fischer Elektronik")
        (field (name "MANUFACTURER PART NUMBER") "ICK BGA 23 x 23 x 10")
      )
      (libsource (lib "Schlib1") (part "Heat Sink No Pad"))
    )
    (comp (ref "IC4")
      (value "XC7A100T-2FGG484C")
      (footprint "FGG484")
      (description "Artix-7 FPGA, 285 User I/Os, 4 GTP, 484-Ball BGA, Speed Grade 2, Commercial Grade, Pb-Free")
      (fields (field (name "GENERIC PART NUMBER") "XC7A100T") (field (name "MANUFACTURER") "Xilinx"))
      (libsource (lib "") (part "XC7A100T-2FGG484C_1"))
    )
    (comp (ref "J8")
      (value "Milli-Grid™")
      (footprint "MOLEX_87831-1420")
      (description "Connector 14 Male")
      (fields
        (field (name "PART NUMBER") "MOLEX_87831-1420")
        (field (name "MANUFACTURER") "MOLEX")
        (field (name "AUTHOR") "CERN DEM JLC")
      )
      (libsource (lib "Connectors") (part "Connector 14 Male"))
    )
    (comp (ref "L4")
      (value "120R@100MHz")
      (footprint "INDC1608X65N")
      (description "Inductor")
      (fields
        (field (name "PART NUMBER") "IND0603_MURATA_BLM18SG121TN1D")
        (field (name "POWER") "3A")
        (field (name "AUTHOR") "CERN DEM JLC")
      )
      (libsource (lib "Inductors & Transformers") (part "Inductor"))
    )
    (comp (ref "L5")
      (value "120R@100MHz")
      (footprint "INDC1608X65N")
      (description "Inductor")
      (fields
        (field (name "PART NUMBER") "IND0603_MURATA_BLM18SG121TN1D")
        (field (name "POWER") "3A")
        (field (name "AUTHOR") "CERN DEM JLC")
      )
      (libsource (lib "Inductors & Transformers") (part "Inductor"))
    )
    (comp (ref "LD3")
      (value "~")
      (footprint "LED_KINGBRIGHT_KPH-1608CGCK")
      (description "LED Green 1A 2C")
      (fields (field (name "MANUFACTURER PART NUMBER") "KPH-1608CGCK"))
      (libsource (lib "Schlib1") (part "KINGBRIGHT_KPTR-3216CGCK"))
    )
    (comp (ref "R46")
      (value "0")
      (footprint "RESC1005X40N")
      (description "Resistor")
      (fields
        (field (name "PART NUMBER") "R0402_0R_JUMPER")
        (field (name "MANUFACTURER") "GENERIC")
        (field (name "AUTHOR") "CERN DEM JLC")
      )
      (libsource (lib "Resistors") (part "Resistor"))
    )
    (comp (ref "R47")
      (value "0")
      (footprint "RESC1005X40N")
      (description "Resistor")
      (fields
        (field (name "PART NUMBER") "R0402_0R_JUMPER")
        (field (name "MANUFACTURER") "GENERIC")
        (field (name "AUTHOR") "CERN DEM JLC")
      )
      (libsource (lib "Resistors") (part "Resistor"))
    )
    (comp (ref "R48")
      (value "0")
      (footprint "RESC1005X40N")
      (description "Resistor")
      (fields
        (field (name "PART NUMBER") "R0402_0R_JUMPER")
        (field (name "MANUFACTURER") "GENERIC")
        (field (name "AUTHOR") "CERN DEM JLC")
      )
      (libsource (lib "Resistors") (part "Resistor"))
    )
    (comp (ref "R52")
      (value "1k")
      (footprint "RESC1005X40N")
      (description "Resistor - 1%")
      (fields
        (field (name "PART NUMBER") "R0402_1K_1%_0.0625W_100PPM")
        (field (name "POWER") "0.0625W")
        (field (name "AUTHOR") "CERN DEM JLC")
      )
      (libsource (lib "Resistors") (part "Resistor - 1%"))
    )
    (comp (ref "R53")
      (value "0")
      (footprint "RESC1005X40N")
      (description "Resistor")
      (fields
        (field (name "PART NUMBER") "R0402_0R_JUMPER")
        (field (name "MANUFACTURER") "GENERIC")
        (field (name "AUTHOR") "CERN DEM JLC")
      )
      (libsource (lib "Resistors") (part "Resistor"))
    )
    (comp (ref "R54")
      (value "0")
      (footprint "RESC1005X40N")
      (description "Resistor")
      (fields
        (field (name "PART NUMBER") "R0402_0R_JUMPER")
        (field (name "MANUFACTURER") "GENERIC")
        (field (name "AUTHOR") "CERN DEM JLC")
      )
      (libsource (lib "Resistors") (part "Resistor"))
    )
    (comp (ref "R55")
      (value "1k")
      (footprint "RESC1005X40N")
      (description "Resistor - 1%")
      (fields
        (field (name "PART NUMBER") "R0402_1K_1%_0.0625W_100PPM")
        (field (name "POWER") "0.0625W")
        (field (name "AUTHOR") "CERN DEM JLC")
      )
      (libsource (lib "Resistors") (part "Resistor - 1%"))
    )
    (comp (ref "R56")
      (value "0")
      (footprint "RESC1005X40N")
      (description "Resistor")
      (fields
        (field (name "PART NUMBER") "R0402_0R_JUMPER")
        (field (name "MANUFACTURER") "GENERIC")
        (field (name "AUTHOR") "CERN DEM JLC")
      )
      (libsource (lib "Resistors") (part "Resistor"))
    )
    (comp (ref "R57")
      (value "300")
      (footprint "RESC1005X40N")
      (description "Resistor - 1%")
      (fields
        (field (name "PART NUMBER") "R0402_300R_1%_0.0625W_100PPM")
        (field (name "POWER") "0.0625W")
        (field (name "AUTHOR") "CERN DEM JLC")
      )
      (libsource (lib "Resistors") (part "Resistor - 1%"))
    )
    (comp (ref "R58")
      (value "10k")
      (footprint "RESC1005X40N")
      (description "Resistor - 1%")
      (fields
        (field (name "PART NUMBER") "R0402_10K_1%_0.0625W_100PPM")
        (field (name "POWER") "0.0625W")
        (field (name "AUTHOR") "CERN DEM JLC")
      )
      (libsource (lib "Resistors") (part "Resistor - 1%"))
    )
    (comp (ref "T4")
      (value "BSH103")
      (footprint "SOT95P230X110-3N")
      (description "N-CHANNEL MOSFET WITH DIODE")
      (fields (field (name "MANUFACTURER") "NEXPERIA") (field (name "AUTHOR") "CERN DEM JLC"))
      (libsource (lib "ICs And Semiconductors") (part "N-MOSFET-D 1G 2S 3D"))
    )
  )
  (nets
    (net (code "1") (name "/CFG_CCLK") (class "Default")
      (node (ref "IC4") (pin "L12") (pinfunction "CCLK_0_L12") (pintype "bidirectional"))
    )
    (net (code "2") (name "/CFG_TCK") (class "Default")
      (node (ref "IC4") (pin "V12") (pinfunction "TCK_0_V12") (pintype "input"))
      (node (ref "J8") (pin "6") (pinfunction "6_6") (pintype "bidirectional"))
    )
    (net (code "3") (name "/CFG_TDI") (class "Default")
      (node (ref "IC4") (pin "R13") (pinfunction "TDI_0_R13") (pintype "input"))
      (node (ref "J8") (pin "10") (pinfunction "10_10") (pintype "bidirectional"))
    )
    (net (code "4") (name "/CFG_TDO") (class "Default")
      (node (ref "IC4") (pin "U13") (pinfunction "TDO_0_U13") (pintype "output"))
      (node (ref "J8") (pin "8") (pinfunction "8_8") (pintype "bidirectional"))
    )
    (net (code "5") (name "/CFG_TMS") (class "Default")
      (node (ref "IC4") (pin "T13") (pinfunction "TMS_0_T13") (pintype "input"))
      (node (ref "J8") (pin "4") (pinfunction "4_4") (pintype "bidirectional"))
    )
    (net (code "6") (name "/DXN_0") (class "Default")
      (node (ref "IC4") (pin "N9") (pinfunction "DXN_0_N9") (pintype "input"))
      (node (ref "R56") (pin "1") (pinfunction "1_1") (pintype "passive"))
    )
    (net (code "7") (name "/DXP_0") (class "Default")
      (node (ref "IC4") (pin "N10") (pinfunction "DXP_0_N10") (pintype "input"))
      (node (ref "R54") (pin "1") (pinfunction "1_1") (pintype "passive"))
    )
    (net (code "8") (name "/EN_USB_JTAG") (class "Default")
      (node (ref "C53") (pin "2") (pinfunction "2_2") (pintype "passive"))
      (node (ref "J8") (pin "13") (pinfunction "13_13") (pintype "bidirectional"))
      (node (ref "R58") (pin "1") (pinfunction "1_1") (pintype "passive"))
    )
    (net (code "9") (name "/FPGA_DONE") (class "Default")
      (node (ref "IC4") (pin "G11") (pinfunction "DONE_0_G11") (pintype "bidirectional"))
      (node (ref "R57") (pin "1") (pinfunction "1_1") (pintype "passive"))
      (node (ref "T4") (pin "1") (pinfunction "G_1") (pintype "passive"))
    )
    (net (code "10") (name "/FPGA_INIT_B") (class "Default")
      (node (ref "IC4") (pin "U12") (pinfunction "INIT_B_0_U12") (pintype "bidirectional"))
      (node (ref "R53") (pin "2") (pinfunction "2_2") (pintype "passive"))
    )
    (net (code "11") (name "/RESETn") (class "Default")
      (node (ref "R53") (pin "1") (pinfunction "1_1") (pintype "passive"))
    )
    (net (code "12") (name "/XADC_GND") (class "Default")
      (node (ref "C50") (pin "1") (pinfunction "1_1") (pintype "passive"))
      (node (ref "C51") (pin "1") (pinfunction "1_1") (pintype "passive"))
      (node (ref "IC4") (pin "K9") (pinfunction "GNDADC_0_K9") (pintype "power_in"))
      (node (ref "IC4") (pin "L10") (pinfunction "VP_0_L10") (pintype "input"))
      (node (ref "IC4") (pin "L9") (pinfunction "VREFN_0_L9") (pintype "input"))
      (node (ref "IC4") (pin "M10") (pinfunction "VREFP_0_M10") (pintype "input"))
      (node (ref "IC4") (pin "M9") (pinfunction "VN_0_M9") (pintype "input"))
      (node (ref "L5") (pin "2") (pinfunction "2_2") (pintype "passive"))
    )
    (net (code "13") (name "/XADC_VCC") (class "Default")
      (node (ref "C50") (pin "2") (pinfunction "2_2") (pintype "passive"))
      (node (ref "C51") (pin "2") (pinfunction "2_2") (pintype "passive"))
      (node (ref "IC4") (pin "K10") (pinfunction "VCCADC_0_K10") (pintype "power_in"))
      (node (ref "L4") (pin "2") (pinfunction "2_2") (pintype "passive"))
    )
    (net (code "14") (name "GND") (class "Default")
      (node (ref "C100") (pin "1") (pinfunction "1_1") (pintype "passive"))
      (node (ref "C101") (pin "1") (pinfunction "1_1") (pintype "passive"))
      (node (ref "C102") (pin "1") (pinfunction "1_1") (pintype "passive"))
      (node (ref "C103") (pin "1") (pinfunction "1_1") (pintype "passive"))
      (node (ref "C104") (pin "1") (pinfunction "1_1") (pintype "passive"))
      (node (ref "C105") (pin "1") (pinfunction "1_1") (pintype "passive"))
      (node (ref "C106") (pin "1") (pinfunction "1_1") (pintype "passive"))
      (node (ref "C107") (pin "1") (pinfunction "1_1") (pintype "passive"))
      (node (ref "C108") (pin "1") (pinfunction "1_1") (pintype "passive"))
      (node (ref "C109") (pin "1") (pinfunction "1_1") (pintype "passive"))
      (node (ref "C110") (pin "1") (pinfunction "1_1") (pintype "passive"))
      (node (ref "C111") (pin "1") (pinfunction "1_1") (pintype "passive"))
      (node (ref "C112") (pin "1") (pinfunction "1_1") (pintype "passive"))
      (node (ref "C113") (pin "1") (pinfunction "1_1") (pintype "passive"))
      (node (ref "C114") (pin "1") (pinfunction "1_1") (pintype "passive"))
      (node (ref "C115") (pin "1") (pinfunction "1_1") (pintype "passive"))
      (node (ref "C116") (pin "1") (pinfunction "1_1") (pintype "passive"))
      (node (ref "C117") (pin "1") (pinfunction "1_1") (pintype "passive"))
      (node (ref "C118") (pin "1") (pinfunction "1_1") (pintype "passive"))
      (node (ref "C119") (pin "1") (pinfunction "1_1") (pintype "passive"))
      (node (ref "C120") (pin "1") (pinfunction "1_1") (pintype "passive"))
      (node (ref "C121") (pin "1") (pinfunction "1_1") (pintype "passive"))
      (node (ref "C122") (pin "1") (pinfunction "1_1") (pintype "passive"))
      (node (ref "C123") (pin "1") (pinfunction "1_1") (pintype "passive"))
      (node (ref "C124") (pin "1") (pinfunction "1_1") (pintype "passive"))
      (node (ref "C125") (pin "1") (pinfunction "1_1") (pintype "passive"))
      (node (ref "C235") (pin "1") (pinfunction "1_1") (pintype "passive"))
      (node (ref "C240") (pin "1") (pinfunction "1_1") (pintype "passive"))
      (node (ref "C52") (pin "1") (pinfunction "1_1") (pintype "passive"))
      (node (ref "C53") (pin "1") (pinfunction "1_1") (pintype "passive"))
      (node (ref "C54") (pin "1") (pinfunction "1_1") (pintype "passive"))
      (node (ref "C55") (pin "1") (pinfunction "1_1") (pintype "passive"))
      (node (ref "C56") (pin "1") (pinfunction "1_1") (pintype "passive"))
      (node (ref "C57") (pin "1") (pinfunction "1_1") (pintype "passive"))
      (node (ref "C58") (pin "1") (pinfunction "1_1") (pintype "passive"))
      (node (ref "C59") (pin "1") (pinfunction "1_1") (pintype "passive"))
      (node (ref "C60") (pin "1") (pinfunction "1_1") (pintype "passive"))
      (node (ref "C61") (pin "1") (pinfunction "1_1") (pintype "passive"))
      (node (ref "C62") (pin "1") (pinfunction "1_1") (pintype "passive"))
      (node (ref "C63") (pin "1") (pinfunction "1_1") (pintype "passive"))
      (node (ref "C64") (pin "1") (pinfunction "1_1") (pintype "passive"))
      (node (ref "C65") (pin "1") (pinfunction "1_1") (pintype "passive"))
      (node (ref "C66") (pin "1") (pinfunction "1_1") (pintype "passive"))
      (node (ref "C67") (pin "1") (pinfunction "1_1") (pintype "passive"))
      (node (ref "C68") (pin "1") (pinfunction "1_1") (pintype "passive"))
      (node (ref "C69") (pin "1") (pinfunction "1_1") (pintype "passive"))
      (node (ref "C70") (pin "1") (pinfunction "1_1") (pintype "passive"))
      (node (ref "C71") (pin "1") (pinfunction "1_1") (pintype "passive"))
      (node (ref "C72") (pin "1") (pinfunction "1_1") (pintype "passive"))
      (node (ref "C73") (pin "1") (pinfunction "1_1") (pintype "passive"))
      (node (ref "C74") (pin "1") (pinfunction "1_1") (pintype "passive"))
      (node (ref "C75") (pin "1") (pinfunction "1_1") (pintype "passive"))
      (node (ref "C76") (pin "1") (pinfunction "1_1") (pintype "passive"))
      (node (ref "C77") (pin "1") (pinfunction "1_1") (pintype "passive"))
      (node (ref "C78") (pin "1") (pinfunction "1_1") (pintype "passive"))
      (node (ref "C79") (pin "1") (pinfunction "1_1") (pintype "passive"))
      (node (ref "C80") (pin "1") (pinfunction "1_1") (pintype "passive"))
      (node (ref "C81") (pin "1") (pinfunction "1_1") (pintype "passive"))
      (node (ref "C82") (pin "1") (pinfunction "1_1") (pintype "passive"))
      (node (ref "C83") (pin "1") (pinfunction "1_1") (pintype "passive"))
      (node (ref "C84") (pin "1") (pinfunction "1_1") (pintype "passive"))
      (node (ref "C85") (pin "1") (pinfunction "1_1") (pintype "passive"))
      (node (ref "C86") (pin "1") (pinfunction "1_1") (pintype "passive"))
      (node (ref "C87") (pin "1") (pinfunction "1_1") (pintype "passive"))
      (node (ref "C88") (pin "1") (pinfunction "1_1") (pintype "passive"))
      (node (ref "C89") (pin "1") (pinfunction "1_1") (pintype "passive"))
      (node (ref "C90") (pin "1") (pinfunction "1_1") (pintype "passive"))
      (node (ref "C91") (pin "2") (pinfunction "2_2") (pintype "passive"))
      (node (ref "C92") (pin "1") (pinfunction "1_1") (pintype "passive"))
      (node (ref "C93") (pin "1") (pinfunction "1_1") (pintype "passive"))
      (node (ref "C94") (pin "1") (pinfunction "1_1") (pintype "passive"))
      (node (ref "C95") (pin "1") (pinfunction "1_1") (pintype "passive"))
      (node (ref "C96") (pin "1") (pinfunction "1_1") (pintype "passive"))
      (node (ref "C97") (pin "1") (pinfunction "1_1") (pintype "passive"))
      (node (ref "C98") (pin "1") (pinfunction "1_1") (pintype "passive"))
      (node (ref "C99") (pin "1") (pinfunction "1_1") (pintype "passive"))
      (node (ref "IC4") (pin "A11") (pinfunction "GND_A11") (pintype "power_in"))
      (node (ref "IC4") (pin "A12") (pinfunction "GND_A12") (pintype "power_in"))
      (node (ref "IC4") (pin "A2") (pinfunction "GND_A2") (pintype "power_in"))
      (node (ref "IC4") (pin "A22") (pinfunction "GND_A22") (pintype "power_in"))
      (node (ref "IC4") (pin "A3") (pinfunction "GND_A3") (pintype "power_in"))
      (node (ref "IC4") (pin "A5") (pinfunction "GND_A5") (pintype "power_in"))
      (node (ref "IC4") (pin "A7") (pinfunction "GND_A7") (pintype "power_in"))
      (node (ref "IC4") (pin "A9") (pinfunction "GND_A9") (pintype "power_in"))
      (node (ref "IC4") (pin "AA12") (pinfunction "GND_AA12") (pintype "power_in"))
      (node (ref "IC4") (pin "AA2") (pinfunction "GND_AA2") (pintype "power_in"))
      (node (ref "IC4") (pin "AA22") (pinfunction "GND_AA22") (pintype "power_in"))
      (node (ref "IC4") (pin "AB19") (pinfunction "GND_AB19") (pintype "power_in"))
      (node (ref "IC4") (pin "AB9") (pinfunction "GND_AB9") (pintype "power_in"))
      (node (ref "IC4") (pin "B12") (pinfunction "GND_B12") (pintype "power_in"))
      (node (ref "IC4") (pin "B19") (pinfunction "GND_B19") (pintype "power_in"))
      (node (ref "IC4") (pin "B3") (pinfunction "GND_B3") (pintype "power_in"))
      (node (ref "IC4") (pin "C10") (pinfunction "GND_C10") (pintype "power_in"))
      (node (ref "IC4") (pin "C12") (pinfunction "GND_C12") (pintype "power_in"))
      (node (ref "IC4") (pin "C16") (pinfunction "GND_C16") (pintype "power_in"))
      (node (ref "IC4") (pin "C3") (pinfunction "GND_C3") (pintype "power_in"))
      (node (ref "IC4") (pin "C6") (pinfunction "GND_C6") (pintype "power_in"))
      (node (ref "IC4") (pin "D12") (pinfunction "GND_D12") (pintype "power_in"))
      (node (ref "IC4") (pin "D13") (pinfunction "GND_D13") (pintype "power_in"))
      (node (ref "IC4") (pin "D3") (pinfunction "GND_D3") (pintype "power_in"))
      (node (ref "IC4") (pin "D4") (pinfunction "GND_D4") (pintype "power_in"))
      (node (ref "IC4") (pin "D8") (pinfunction "GND_D8") (pintype "power_in"))
      (node (ref "IC4") (pin "E11") (pinfunction "GND_E11") (pintype "power_in"))
      (node (ref "IC4") (pin "E12") (pinfunction "VCCBATT_0_E12") (pintype "power_in"))
      (node (ref "IC4") (pin "E20") (pinfunction "GND_E20") (pintype "power_in"))
      (node (ref "IC4") (pin "E4") (pinfunction "GND_E4") (pintype "power_in"))
      (node (ref "IC4") (pin "E5") (pinfunction "GND_E5") (pintype "power_in"))
      (node (ref "IC4") (pin "E7") (pinfunction "GND_E7") (pintype "power_in"))
      (node (ref "IC4") (pin "E9") (pinfunction "GND_E9") (pintype "power_in"))
      (node (ref "IC4") (pin "F11") (pinfunction "GND_F11") (pintype "power_in"))
      (node (ref "IC4") (pin "F17") (pinfunction "GND_F17") (pintype "power_in"))
      (node (ref "IC4") (pin "F5") (pinfunction "GND_F5") (pintype "power_in"))
      (node (ref "IC4") (pin "G10") (pinfunction "GND_G10") (pintype "power_in"))
      (node (ref "IC4") (pin "G12") (pinfunction "GND_G12") (pintype "power_in"))
      (node (ref "IC4") (pin "G14") (pinfunction "GND_G14") (pintype "power_in"))
      (node (ref "IC4") (pin "G5") (pinfunction "GND_G5") (pintype "power_in"))
      (node (ref "IC4") (pin "G6") (pinfunction "GND_G6") (pintype "power_in"))
      (node (ref "IC4") (pin "G7") (pinfunction "GND_G7") (pintype "power_in"))
      (node (ref "IC4") (pin "G8") (pinfunction "GND_G8") (pintype "power_in"))
      (node (ref "IC4") (pin "G9") (pinfunction "GND_G9") (pintype "power_in"))
      (node (ref "IC4") (pin "H1") (pinfunction "GND_H1") (pintype "power_in"))
      (node (ref "IC4") (pin "H11") (pinfunction "GND_H11") (pintype "power_in"))
      (node (ref "IC4") (pin "H21") (pinfunction "GND_H21") (pintype "power_in"))
      (node (ref "IC4") (pin "H7") (pinfunction "GND_H7") (pintype "power_in"))
      (node (ref "IC4") (pin "H9") (pinfunction "GND_H9") (pintype "power_in"))
      (node (ref "IC4") (pin "J10") (pinfunction "GND_J10") (pintype "power_in"))
      (node (ref "IC4") (pin "J12") (pinfunction "GND_J12") (pintype "power_in"))
      (node (ref "IC4") (pin "J18") (pinfunction "GND_J18") (pintype "power_in"))
      (node (ref "IC4") (pin "J8") (pinfunction "GND_J8") (pintype "power_in"))
      (node (ref "IC4") (pin "K11") (pinfunction "GND_K11") (pintype "power_in"))
      (node (ref "IC4") (pin "K15") (pinfunction "GND_K15") (pintype "power_in"))
      (node (ref "IC4") (pin "K5") (pinfunction "GND_K5") (pintype "power_in"))
      (node (ref "IC4") (pin "K7") (pinfunction "GND_K7") (pintype "power_in"))
      (node (ref "IC4") (pin "L2") (pinfunction "GND_L2") (pintype "power_in"))
      (node (ref "IC4") (pin "L22") (pinfunction "GND_L22") (pintype "power_in"))
      (node (ref "IC4") (pin "L8") (pinfunction "GND_L8") (pintype "power_in"))
      (node (ref "IC4") (pin "M11") (pinfunction "GND_M11") (pintype "power_in"))
      (node (ref "IC4") (pin "M19") (pinfunction "GND_M19") (pintype "power_in"))
      (node (ref "IC4") (pin "M7") (pinfunction "GND_M7") (pintype "power_in"))
      (node (ref "IC4") (pin "N16") (pinfunction "GND_N16") (pintype "power_in"))
      (node (ref "IC4") (pin "N6") (pinfunction "GND_N6") (pintype "power_in"))
      (node (ref "IC4") (pin "N8") (pinfunction "GND_N8") (pintype "power_in"))
      (node (ref "IC4") (pin "P11") (pinfunction "GND_P11") (pintype "power_in"))
      (node (ref "IC4") (pin "P13") (pinfunction "GND_P13") (pintype "power_in"))
      (node (ref "IC4") (pin "P3") (pinfunction "GND_P3") (pintype "power_in"))
      (node (ref "IC4") (pin "P7") (pinfunction "GND_P7") (pintype "power_in"))
      (node (ref "IC4") (pin "P9") (pinfunction "GND_P9") (pintype "power_in"))
      (node (ref "IC4") (pin "R10") (pinfunction "GND_R10") (pintype "power_in"))
      (node (ref "IC4") (pin "R12") (pinfunction "GND_R12") (pintype "power_in"))
      (node (ref "IC4") (pin "R20") (pinfunction "GND_R20") (pintype "power_in"))
      (node (ref "IC4") (pin "R8") (pinfunction "GND_R8") (pintype "power_in"))
      (node (ref "IC4") (pin "T11") (pinfunction "GND_T11") (pintype "power_in"))
      (node (ref "IC4") (pin "T17") (pinfunction "GND_T17") (pintype "power_in"))
      (node (ref "IC4") (pin "T7") (pinfunction "GND_T7") (pintype "power_in"))
      (node (ref "IC4") (pin "T9") (pinfunction "GND_T9") (pintype "power_in"))
      (node (ref "IC4") (pin "U14") (pinfunction "GND_U14") (pintype "power_in"))
      (node (ref "IC4") (pin "U4") (pinfunction "GND_U4") (pintype "power_in"))
      (node (ref "IC4") (pin "V1") (pinfunction "GND_V1") (pintype "power_in"))
      (node (ref "IC4") (pin "V11") (pinfunction "GND_V11") (pintype "power_in"))
      (node (ref "IC4") (pin "V21") (pinfunction "GND_V21") (pintype "power_in"))
      (node (ref "IC4") (pin "W18") (pinfunction "GND_W18") (pintype "power_in"))
      (node (ref "IC4") (pin "W8") (pinfunction "GND_W8") (pintype "power_in"))
      (node (ref "IC4") (pin "Y15") (pinfunction "GND_Y15") (pintype "power_in"))
      (node (ref "IC4") (pin "Y5") (pinfunction "GND_Y5") (pintype "power_in"))
      (node (ref "J8") (pin "1") (pinfunction "1_1") (pintype "bidirectional"))
      (node (ref "J8") (pin "11") (pinfunction "11_11") (pintype "bidirectional"))
      (node (ref "J8") (pin "3") (pinfunction "3_3") (pintype "bidirectional"))
      (node (ref "J8") (pin "5") (pinfunction "5_5") (pintype "bidirectional"))
      (node (ref "J8") (pin "7") (pinfunction "7_7") (pintype "bidirectional"))
      (node (ref "J8") (pin "9") (pinfunction "9_9") (pintype "bidirectional"))
      (node (ref "L5") (pin "1") (pinfunction "1_1") (pintype "passive"))
      (node (ref "R47") (pin "1") (pinfunction "1_1") (pintype "passive"))
      (node (ref "R48") (pin "1") (pinfunction "1_1") (pintype "passive"))
      (node (ref "R54") (pin "2") (pinfunction "2_2") (pintype "passive"))
      (node (ref "R56") (pin "2") (pinfunction "2_2") (pintype "passive"))
      (node (ref "T4") (pin "2") (pinfunction "S_2") (pintype "passive"))
    )
    (net (code "15") (name "MGTAVCC") (class "Default")
      (node (ref "C100") (pin "2") (pinfunction "2_2") (pintype "passive"))
      (node (ref "C123") (pin "2") (pinfunction "2_2") (pintype "passive"))
      (node (ref "C124") (pin "2") (pinfunction "2_2") (pintype "passive"))
      (node (ref "C125") (pin "2") (pinfunction "2_2") (pintype "passive"))
      (node (ref "C57") (pin "2") (pinfunction "2_2") (pintype "passive"))
      (node (ref "IC4") (pin "D10") (pinfunction "MGTAVCC_D10") (pintype "power_in"))
      (node (ref "IC4") (pin "D6") (pinfunction "MGTAVCC_D6") (pintype "power_in"))
      (node (ref "IC4") (pin "E8") (pinfunction "MGTAVCC_E8") (pintype "power_in"))
      (node (ref "IC4") (pin "F7") (pinfunction "MGTAVCC_F7") (pintype "power_in"))
      (node (ref "IC4") (pin "F9") (pinfunction "MGTAVCC_F9") (pintype "power_in"))
    )
    (net (code "16") (name "MGTAVTT") (class "Default")
      (node (ref "C101") (pin "2") (pinfunction "2_2") (pintype "passive"))
      (node (ref "C112") (pin "2") (pinfunction "2_2") (pintype "passive"))
      (node (ref "C113") (pin "2") (pinfunction "2_2") (pintype "passive"))
      (node (ref "C114") (pin "2") (pinfunction "2_2") (pintype "passive"))
      (node (ref "C115") (pin "2") (pinfunction "2_2") (pintype "passive"))
      (node (ref "C116") (pin "2") (pinfunction "2_2") (pintype "passive"))
      (node (ref "C97") (pin "2") (pinfunction "2_2") (pintype "passive"))
      (node (ref "IC4") (pin "B11") (pinfunction "MGTAVTT_B11") (pintype "power_in"))
      (node (ref "IC4") (pin "B5") (pinfunction "MGTAVTT_B5") (pintype "power_in"))
      (node (ref "IC4") (pin "B7") (pinfunction "MGTAVTT_B7") (pintype "power_in"))
      (node (ref "IC4") (pin "B9") (pinfunction "MGTAVTT_B9") (pintype "power_in"))
      (node (ref "IC4") (pin "C4") (pinfunction "MGTAVTT_C4") (pintype "power_in"))
      (node (ref "IC4") (pin "C8") (pinfunction "MGTAVTT_C8") (pintype "power_in"))
    )
    (net (code "17") (name "Net-(IC4G-M0_0)") (class "Default")
      (node (ref "IC4") (pin "U11") (pinfunction "M0_0_U11") (pintype "input"))
      (node (ref "R46") (pin "2") (pinfunction "2_2") (pintype "passive"))
    )
    (net (code "18") (name "Net-(IC4G-M1_0)") (class "Default")
      (node (ref "IC4") (pin "U10") (pinfunction "M1_0_U10") (pintype "input"))
      (node (ref "R47") (pin "2") (pinfunction "2_2") (pintype "passive"))
    )
    (net (code "19") (name "Net-(IC4G-M2_0)") (class "Default")
      (node (ref "IC4") (pin "U9") (pinfunction "M2_0_U9") (pintype "input"))
      (node (ref "R48") (pin "2") (pinfunction "2_2") (pintype "passive"))
    )
    (net (code "20") (name "Net-(IC4G-PROGRAM_B_0)") (class "Default")
      (node (ref "IC4") (pin "N12") (pinfunction "PROGRAM_B_0_N12") (pintype "input"))
      (node (ref "R52") (pin "2") (pinfunction "2_2") (pintype "passive"))
    )
    (net (code "21") (name "Net-(LD3-A)") (class "Default")
      (node (ref "LD3") (pin "1") (pinfunction "A_1") (pintype "passive"))
      (node (ref "R55") (pin "1") (pinfunction "1_1") (pintype "passive"))
    )
    (net (code "22") (name "Net-(LD3-C)") (class "Default")
      (node (ref "LD3") (pin "2") (pinfunction "C_2") (pintype "passive"))
      (node (ref "T4") (pin "3") (pinfunction "D_3") (pintype "passive"))
    )
    (net (code "23") (name "P1V0") (class "Default")
      (node (ref "C102") (pin "2") (pinfunction "2_2") (pintype "passive"))
      (node (ref "C103") (pin "2") (pinfunction "2_2") (pintype "passive"))
      (node (ref "C104") (pin "2") (pinfunction "2_2") (pintype "passive"))
      (node (ref "C105") (pin "2") (pinfunction "2_2") (pintype "passive"))
      (node (ref "C106") (pin "2") (pinfunction "2_2") (pintype "passive"))
      (node (ref "C107") (pin "2") (pinfunction "2_2") (pintype "passive"))
      (node (ref "C108") (pin "2") (pinfunction "2_2") (pintype "passive"))
      (node (ref "C109") (pin "2") (pinfunction "2_2") (pintype "passive"))
      (node (ref "C110") (pin "2") (pinfunction "2_2") (pintype "passive"))
      (node (ref "C91") (pin "1") (pinfunction "1_1") (pintype "passive"))
      (node (ref "C92") (pin "2") (pinfunction "2_2") (pintype "passive"))
      (node (ref "C93") (pin "2") (pinfunction "2_2") (pintype "passive"))
      (node (ref "C94") (pin "2") (pinfunction "2_2") (pintype "passive"))
      (node (ref "C95") (pin "2") (pinfunction "2_2") (pintype "passive"))
      (node (ref "C96") (pin "2") (pinfunction "2_2") (pintype "passive"))
      (node (ref "IC4") (pin "H10") (pinfunction "VCCINT_H10") (pintype "power_in"))
      (node (ref "IC4") (pin "H8") (pinfunction "VCCINT_H8") (pintype "power_in"))
      (node (ref "IC4") (pin "J7") (pinfunction "VCCINT_J7") (pintype "power_in"))
      (node (ref "IC4") (pin "J9") (pinfunction "VCCINT_J9") (pintype "power_in"))
      (node (ref "IC4") (pin "K8") (pinfunction "VCCINT_K8") (pintype "power_in"))
      (node (ref "IC4") (pin "L7") (pinfunction "VCCINT_L7") (pintype "power_in"))
      (node (ref "IC4") (pin "M8") (pinfunction "VCCINT_M8") (pintype "power_in"))
      (node (ref "IC4") (pin "N7") (pinfunction "VCCINT_N7") (pintype "power_in"))
      (node (ref "IC4") (pin "P10") (pinfunction "VCCINT_P10") (pintype "power_in"))
      (node (ref "IC4") (pin "P8") (pinfunction "VCCINT_P8") (pintype "power_in"))
      (node (ref "IC4") (pin "R7") (pinfunction "VCCINT_R7") (pintype "power_in"))
      (node (ref "IC4") (pin "R9") (pinfunction "VCCINT_R9") (pintype "power_in"))
      (node (ref "IC4") (pin "T10") (pinfunction "VCCINT_T10") (pintype "power_in"))
      (node (ref "IC4") (pin "T8") (pinfunction "VCCINT_T8") (pintype "power_in"))
    )
    (net (code "24") (name "P1V5") (class "Default")
      (node (ref "C240") (pin "2") (pinfunction "2_2") (pintype "passive"))
      (node (ref "C60") (pin "2") (pinfunction "2_2") (pintype "passive"))
      (node (ref "C64") (pin "2") (pinfunction "2_2") (pintype "passive"))
      (node (ref "C81") (pin "2") (pinfunction "2_2") (pintype "passive"))
      (node (ref "C82") (pin "2") (pinfunction "2_2") (pintype "passive"))
      (node (ref "C83") (pin "2") (pinfunction "2_2") (pintype "passive"))
      (node (ref "C84") (pin "2") (pinfunction "2_2") (pintype "passive"))
      (node (ref "C85") (pin "2") (pinfunction "2_2") (pintype "passive"))
      (node (ref "IC4") (pin "C1") (pinfunction "VCCO_35_C1") (pintype "power_in"))
      (node (ref "IC4") (pin "F2") (pinfunction "VCCO_35_F2") (pintype "power_in"))
      (node (ref "IC4") (pin "H6") (pinfunction "VCCO_35_H6") (pintype "power_in"))
      (node (ref "IC4") (pin "J3") (pinfunction "VCCO_35_J3") (pintype "power_in"))
      (node (ref "IC4") (pin "M4") (pinfunction "VCCO_35_M4") (pintype "power_in"))
      (node (ref "IC4") (pin "N1") (pinfunction "VCCO_35_N1") (pintype "power_in"))
    )
    (net (code "25") (name "P1V8") (class "Default")
      (node (ref "L4") (pin "1") (pinfunction "1_1") (pintype "passive"))
    )
    (net (code "26") (name "P2V5") (class "Default")
      (node (ref "C52") (pin "2") (pinfunction "2_2") (pintype "passive"))
      (node (ref "C54") (pin "2") (pinfunction "2_2") (pintype "passive"))
      (node (ref "C58") (pin "2") (pinfunction "2_2") (pintype "passive"))
      (node (ref "C61") (pin "2") (pinfunction "2_2") (pintype "passive"))
      (node (ref "C62") (pin "2") (pinfunction "2_2") (pintype "passive"))
      (node (ref "C63") (pin "2") (pinfunction "2_2") (pintype "passive"))
      (node (ref "C65") (pin "2") (pinfunction "2_2") (pintype "passive"))
      (node (ref "C66") (pin "2") (pinfunction "2_2") (pintype "passive"))
      (node (ref "C67") (pin "2") (pinfunction "2_2") (pintype "passive"))
      (node (ref "C68") (pin "2") (pinfunction "2_2") (pintype "passive"))
      (node (ref "C69") (pin "2") (pinfunction "2_2") (pintype "passive"))
      (node (ref "C70") (pin "2") (pinfunction "2_2") (pintype "passive"))
      (node (ref "C71") (pin "2") (pinfunction "2_2") (pintype "passive"))
      (node (ref "C72") (pin "2") (pinfunction "2_2") (pintype "passive"))
      (node (ref "C73") (pin "2") (pinfunction "2_2") (pintype "passive"))
      (node (ref "C74") (pin "2") (pinfunction "2_2") (pintype "passive"))
      (node (ref "C75") (pin "2") (pinfunction "2_2") (pintype "passive"))
      (node (ref "C76") (pin "2") (pinfunction "2_2") (pintype "passive"))
      (node (ref "C77") (pin "2") (pinfunction "2_2") (pintype "passive"))
      (node (ref "C78") (pin "2") (pinfunction "2_2") (pintype "passive"))
      (node (ref "C79") (pin "2") (pinfunction "2_2") (pintype "passive"))
      (node (ref "C80") (pin "2") (pinfunction "2_2") (pintype "passive"))
      (node (ref "C86") (pin "2") (pinfunction "2_2") (pintype "passive"))
      (node (ref "C87") (pin "2") (pinfunction "2_2") (pintype "passive"))
      (node (ref "C88") (pin "2") (pinfunction "2_2") (pintype "passive"))
      (node (ref "C89") (pin "2") (pinfunction "2_2") (pintype "passive"))
      (node (ref "C90") (pin "2") (pinfunction "2_2") (pintype "passive"))
      (node (ref "IC4") (pin "A17") (pinfunction "VCCO_16_A17") (pintype "power_in"))
      (node (ref "IC4") (pin "AA17") (pinfunction "VCCO_13_AA17") (pintype "power_in"))
      (node (ref "IC4") (pin "AA7") (pinfunction "VCCO_34_AA7") (pintype "power_in"))
      (node (ref "IC4") (pin "AB14") (pinfunction "VCCO_13_AB14") (pintype "power_in"))
      (node (ref "IC4") (pin "AB4") (pinfunction "VCCO_34_AB4") (pintype "power_in"))
      (node (ref "IC4") (pin "B14") (pinfunction "VCCO_16_B14") (pintype "power_in"))
      (node (ref "IC4") (pin "C21") (pinfunction "VCCO_16_C21") (pintype "power_in"))
      (node (ref "IC4") (pin "D18") (pinfunction "VCCO_16_D18") (pintype "power_in"))
      (node (ref "IC4") (pin "E15") (pinfunction "VCCO_16_E15") (pintype "power_in"))
      (node (ref "IC4") (pin "F12") (pinfunction "VCCO_0_F12") (pintype "power_in"))
      (node (ref "IC4") (pin "F22") (pinfunction "VCCO_16_F22") (pintype "power_in"))
      (node (ref "IC4") (pin "G19") (pinfunction "VCCO_15_G19") (pintype "power_in"))
      (node (ref "IC4") (pin "H16") (pinfunction "VCCO_15_H16") (pintype "power_in"))
      (node (ref "IC4") (pin "J13") (pinfunction "VCCO_15_J13") (pintype "power_in"))
      (node (ref "IC4") (pin "K20") (pinfunction "VCCO_15_K20") (pintype "power_in"))
      (node (ref "IC4") (pin "L17") (pinfunction "VCCO_15_L17") (pintype "power_in"))
      (node (ref "IC4") (pin "M14") (pinfunction "VCCO_14_M14") (pintype "power_in"))
      (node (ref "IC4") (pin "N21") (pinfunction "VCCO_15_N21") (pintype "power_in"))
      (node (ref "IC4") (pin "P18") (pinfunction "VCCO_14_P18") (pintype "power_in"))
      (node (ref "IC4") (pin "R15") (pinfunction "VCCO_14_R15") (pintype "power_in"))
      (node (ref "IC4") (pin "R5") (pinfunction "VCCO_34_R5") (pintype "power_in"))
      (node (ref "IC4") (pin "T12") (pinfunction "VCCO_0_T12") (pintype "power_in"))
      (node (ref "IC4") (pin "T2") (pinfunction "VCCO_34_T2") (pintype "power_in"))
      (node (ref "IC4") (pin "T22") (pinfunction "VCCO_14_T22") (pintype "power_in"))
      (node (ref "IC4") (pin "U19") (pinfunction "VCCO_14_U19") (pintype "power_in"))
      (node (ref "IC4") (pin "U8") (pinfunction "CFGBVS_0_U8") (pintype "input"))
      (node (ref "IC4") (pin "V16") (pinfunction "VCCO_13_V16") (pintype "power_in"))
      (node (ref "IC4") (pin "V6") (pinfunction "VCCO_34_V6") (pintype "power_in"))
      (node (ref "IC4") (pin "W13") (pinfunction "VCCO_13_W13") (pintype "power_in"))
      (node (ref "IC4") (pin "W3") (pinfunction "VCCO_34_W3") (pintype "power_in"))
      (node (ref "IC4") (pin "Y10") (pinfunction "VCCO_13_Y10") (pintype "power_in"))
      (node (ref "IC4") (pin "Y20") (pinfunction "VCCO_14_Y20") (pintype "power_in"))
      (node (ref "J8") (pin "2") (pinfunction "2_2") (pintype "bidirectional"))
      (node (ref "R46") (pin "1") (pinfunction "1_1") (pintype "passive"))
      (node (ref "R52") (pin "1") (pinfunction "1_1") (pintype "passive"))
      (node (ref "R57") (pin "2") (pinfunction "2_2") (pintype "passive"))
      (node (ref "R58") (pin "2") (pinfunction "2_2") (pintype "passive"))
    )
    (net (code "27") (name "P3V3") (class "Default")
      (node (ref "R55") (pin "2") (pinfunction "2_2") (pintype "passive"))
    )
    (net (code "28") (name "VCCAUX") (class "Default")
      (node (ref "C111") (pin "2") (pinfunction "2_2") (pintype "passive"))
      (node (ref "C117") (pin "2") (pinfunction "2_2") (pintype "passive"))
      (node (ref "C118") (pin "2") (pinfunction "2_2") (pintype "passive"))
      (node (ref "C119") (pin "2") (pinfunction "2_2") (pintype "passive"))
      (node (ref "C235") (pin "2") (pinfunction "2_2") (pintype "passive"))
      (node (ref "C55") (pin "2") (pinfunction "2_2") (pintype "passive"))
      (node (ref "C59") (pin "2") (pinfunction "2_2") (pintype "passive"))
      (node (ref "C98") (pin "2") (pinfunction "2_2") (pintype "passive"))
      (node (ref "IC4") (pin "H12") (pinfunction "VCCAUX_H12") (pintype "power_in"))
      (node (ref "IC4") (pin "K12") (pinfunction "VCCAUX_K12") (pintype "power_in"))
      (node (ref "IC4") (pin "M12") (pinfunction "VCCAUX_M12") (pintype "power_in"))
      (node (ref "IC4") (pin "P12") (pinfunction "VCCAUX_P12") (pintype "power_in"))
      (node (ref "IC4") (pin "R11") (pinfunction "VCCAUX_R11") (pintype "power_in"))
    )
    (net (code "29") (name "VCCBRAM") (class "Default")
      (node (ref "C120") (pin "2") (pinfunction "2_2") (pintype "passive"))
      (node (ref "C121") (pin "2") (pinfunction "2_2") (pintype "passive"))
      (node (ref "C122") (pin "2") (pinfunction "2_2") (pintype "passive"))
      (node (ref "C56") (pin "2") (pinfunction "2_2") (pintype "passive"))
      (node (ref "C99") (pin "2") (pinfunction "2_2") (pintype "passive"))
      (node (ref "IC4") (pin "J11") (pinfunction "VCCBRAM_J11") (pintype "power_in"))
      (node (ref "IC4") (pin "L11") (pinfunction "VCCBRAM_L11") (pintype "power_in"))
      (node (ref "IC4") (pin "N11") (pinfunction "VCCBRAM_N11") (pintype "power_in"))
    )
    (net (code "30") (name "unconnected-(J8-Pad12)") (class "Default")
      (node (ref "J8") (pin "12") (pinfunction "12_12") (pintype "bidirectional+no_connect"))
    )
    (net (code "31") (name "unconnected-(J8-Pad14)") (class "Default")
      (node (ref "J8") (pin "14") (pinfunction "14_14") (pintype "bidirectional+no_connect"))
    )
  )
)
